# power.net
KiCad netlist of a schematic drawn in EAGLE
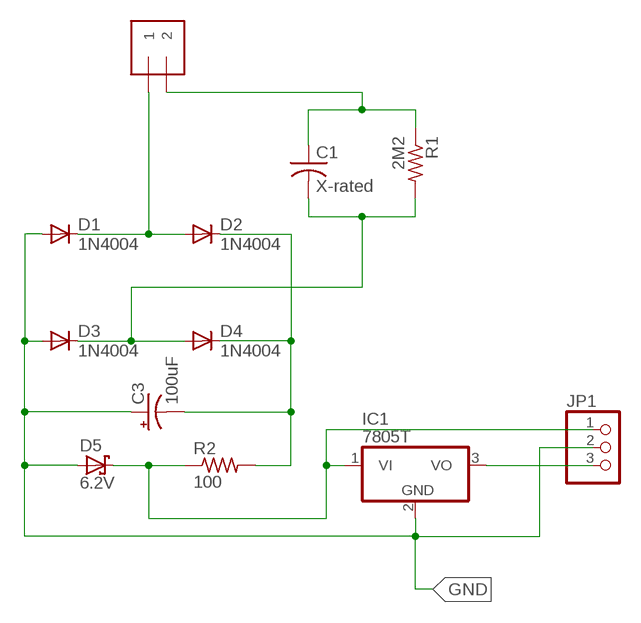
[diagram p0: schematic, sheet 1]

(export (version "E")
  (design (tool "Eeschema 10.0.6"))
  (components
    (comp (ref "C1")
      (value "X-rated")
      (footprint "eagle-import:C225-108X268")
      (libsource (lib "eagle-import") (part "C-US225-108X268"))
    )
    (comp (ref "C3")
      (value "100uF")
      (footprint "eagle-import:E2,5-5")
      (fields (field (name "MPN") "ECA-1EHG101"))
      (libsource (lib "eagle-import") (part "CPOL-USE2.5-5"))
    )
    (comp (ref "D1")
      (value "1N4004")
      (footprint "eagle-import:DO41-10")
      (fields (field (name "MPN") "1N4007RLG"))
      (libsource (lib "eagle-import") (part "1N4004"))
    )
    (comp (ref "D2")
      (value "1N4004")
      (footprint "eagle-import:DO41-10")
      (fields (field (name "MPN") "1N4007RLG"))
      (libsource (lib "eagle-import") (part "1N4004"))
    )
    (comp (ref "D3")
      (value "1N4004")
      (footprint "eagle-import:DO41-10")
      (fields (field (name "MPN") "1N4007RLG"))
      (libsource (lib "eagle-import") (part "1N4004"))
    )
    (comp (ref "D4")
      (value "1N4004")
      (footprint "eagle-import:DO41-10")
      (fields (field (name "MPN") "1N4007RLG"))
      (libsource (lib "eagle-import") (part "1N4004"))
    )
    (comp (ref "D5")
      (value "6.2V")
      (footprint "eagle-import:DO41-7")
      (fields (field (name "MF") "AMERICAN POWER DEVICES") (field (name "MPN") "1N823A"))
      (libsource (lib "eagle-import") (part "SCHOTTKY-DIODEDO41-7"))
    )
    (comp (ref "IC1")
      (value "7805T")
      (footprint "eagle-import:TO220H")
      (fields (field (name "MF") "FAIRCHILD SEMICONDUCTOR") (field (name "MPN") "KA7805AETU"))
      (libsource (lib "eagle-import") (part "78T05"))
    )
    (comp (ref "J1")
      (value "1X2-3.5MM")
      (footprint "eagle-import:1X2-3.5MM")
      (libsource (lib "eagle-import") (part "1X2-3.5MM"))
    )
    (comp (ref "JP1")
      (value "PINHD-1X3CB")
      (footprint "eagle-import:1X03-CLEANBIG")
      (libsource (lib "eagle-import") (part "PINHD-1X3CB"))
    )
    (comp (ref "R1")
      (value "2M2")
      (footprint "eagle-import:0207_10")
      (fields (field (name "MPN") "CRCW08052M20JNEA"))
      (libsource (lib "eagle-import") (part "R-US_0207/10"))
    )
    (comp (ref "R2")
      (value "100")
      (footprint "eagle-import:0207_10")
      (fields (field (name "MF") "OHMITE") (field (name "MPN") "25J100E"))
      (libsource (lib "eagle-import") (part "R-US_0207/10"))
    )
  )
  (nets
    (net (code "1") (name "GND") (class "Default")
      (node (ref "C3") (pin "+") (pinfunction "+_+") (pintype "passive"))
      (node (ref "D1") (pin "A") (pinfunction "A_A") (pintype "passive"))
      (node (ref "D3") (pin "A") (pinfunction "A_A") (pintype "passive"))
      (node (ref "D5") (pin "A") (pinfunction "A_A") (pintype "passive"))
      (node (ref "IC1") (pin "2") (pinfunction "GND_2") (pintype "passive"))
      (node (ref "JP1") (pin "2") (pinfunction "2_2") (pintype "passive"))
    )
    (net (code "2") (name "Net-(C1-Pad1)") (class "Default")
      (node (ref "C1") (pin "1") (pinfunction "1_1") (pintype "passive"))
      (node (ref "J1") (pin "2") (pinfunction "2_2") (pintype "passive"))
      (node (ref "R1") (pin "1") (pinfunction "1_1") (pintype "passive"))
    )
    (net (code "3") (name "Net-(C1-Pad2)") (class "Default")
      (node (ref "C1") (pin "2") (pinfunction "2_2") (pintype "passive"))
      (node (ref "D3") (pin "C") (pinfunction "C_C") (pintype "passive"))
      (node (ref "D4") (pin "A") (pinfunction "A_A") (pintype "passive"))
      (node (ref "R1") (pin "2") (pinfunction "2_2") (pintype "passive"))
    )
    (net (code "4") (name "Net-(C3-Pad-)") (class "Default")
      (node (ref "C3") (pin "-") (pinfunction "-_-") (pintype "passive"))
      (node (ref "D2") (pin "C") (pinfunction "C_C") (pintype "passive"))
      (node (ref "D4") (pin "C") (pinfunction "C_C") (pintype "passive"))
      (node (ref "R2") (pin "2") (pinfunction "2_2") (pintype "passive"))
    )
    (net (code "5") (name "Net-(D1-PadC)") (class "Default")
      (node (ref "D1") (pin "C") (pinfunction "C_C") (pintype "passive"))
      (node (ref "D2") (pin "A") (pinfunction "A_A") (pintype "passive"))
      (node (ref "J1") (pin "1") (pinfunction "1_1") (pintype "passive"))
    )
    (net (code "6") (name "Net-(IC1-VI)") (class "Default")
      (node (ref "D5") (pin "C") (pinfunction "C_C") (pintype "passive"))
      (node (ref "IC1") (pin "1") (pinfunction "VI_1") (pintype "input"))
      (node (ref "JP1") (pin "1") (pinfunction "1_1") (pintype "passive"))
      (node (ref "R2") (pin "1") (pinfunction "1_1") (pintype "passive"))
    )
    (net (code "7") (name "Net-(IC1-VO)") (class "Default")
      (node (ref "IC1") (pin "3") (pinfunction "VO_3") (pintype "passive"))
      (node (ref "JP1") (pin "3") (pinfunction "3_3") (pintype "passive"))
    )
  )
)
